# GreenHouse_BOX.net
KiCad netlist of a schematic drawn in EasyEDA
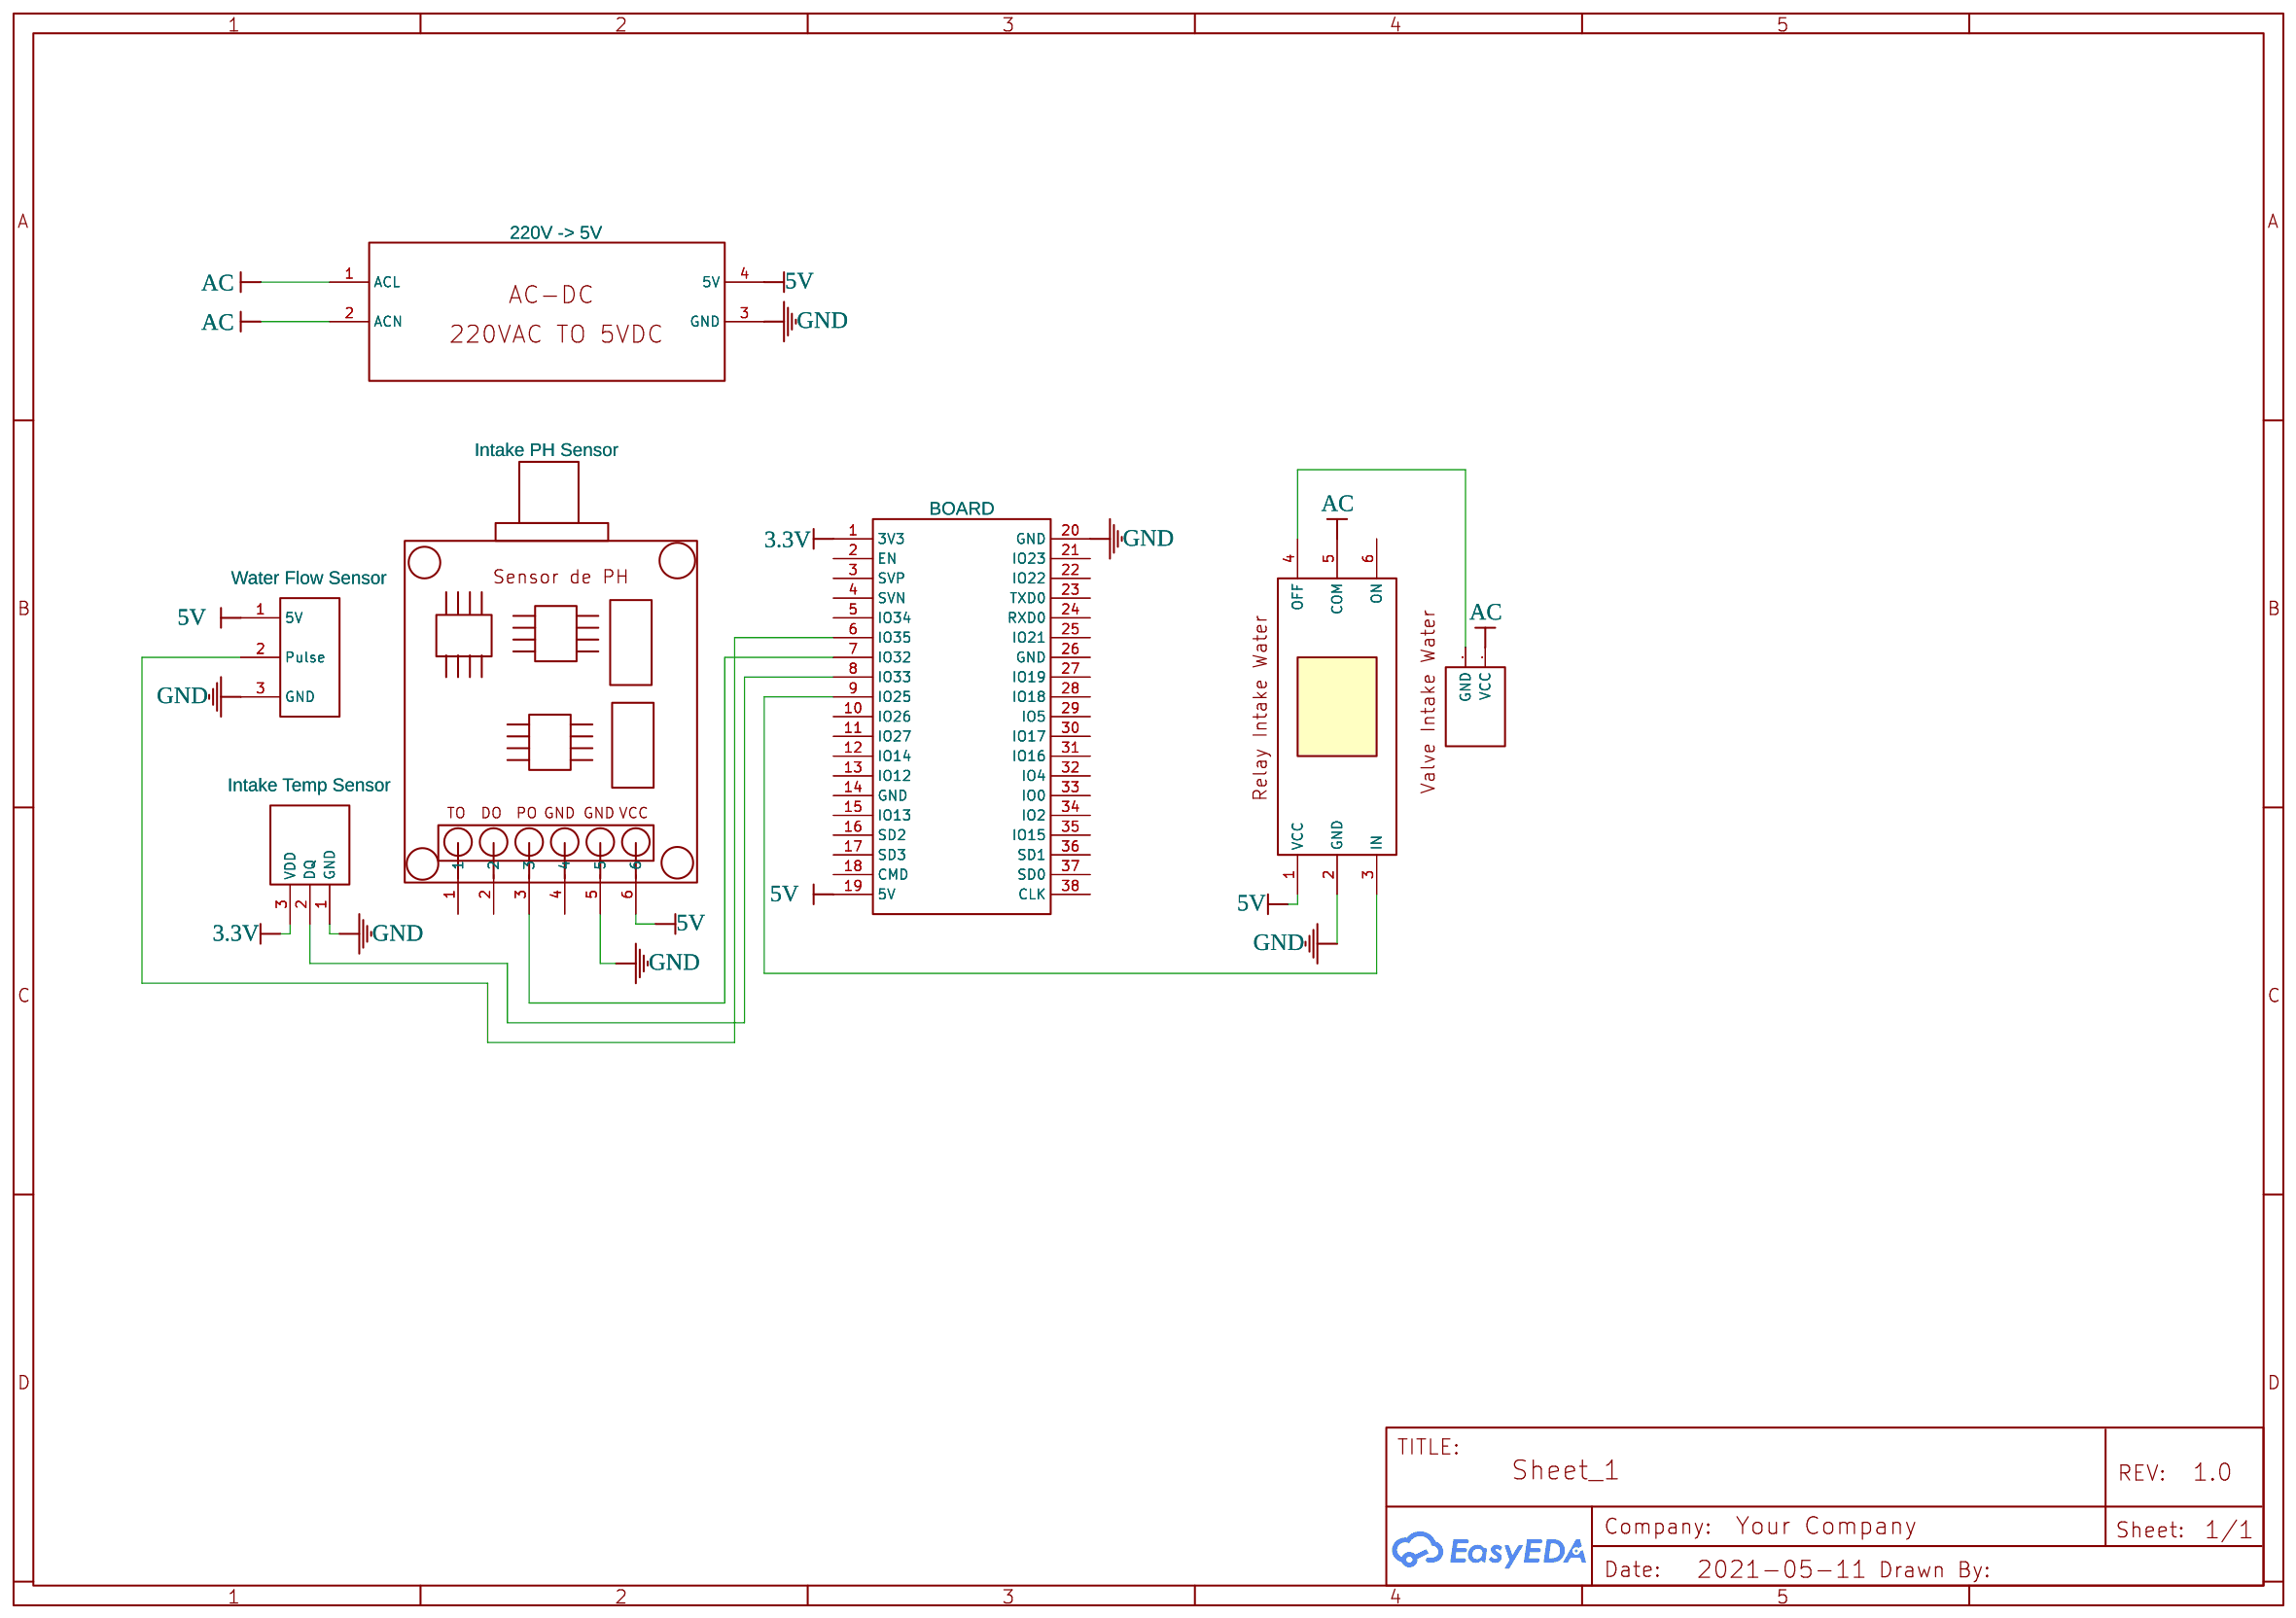
[diagram p0: schematic sheet]

(export (version "E")
  (design (tool "Eeschema 10.0.6"))
  (components
    (comp (ref "BOARD") (value "ESP32") (libsource (lib "") (part "ESP32")))
    (comp (ref "BT1FF")
      (value "Intake Temp Sensor")
      (fields (field (name "BOM_Manufacturer Part") "DS18B20+") (field (name "BOM_Supplier Part") "C9753"))
      (libsource (lib "") (part "DS18B20"))
    )
    (comp (ref "P1")
      (value "Solenoid Valve")
      (fields
        (field (name "BOM_Manufacturer Part") "Header2.54mm 1*3P")
        (field (name "BOM_Supplier Part") "C49257")
      )
      (libsource (lib "") (part "Solenoid Valve"))
    )
    (comp (ref "U1")
      (value "Intake PH Sensor")
      (fields (field (name "BOM_Manufacturer Part") "New SchematicLib"))
      (libsource (lib "") (part "PH Sensor"))
    )
    (comp (ref "U2")
      (value "220V -> 5V")
      (fields (field (name "BOM_Manufacturer Part") "ACDC_220V_5V"))
      (libsource (lib "") (part "ACDC_220V_5V"))
    )
    (comp (ref "U3")
      (value "Arduino Relay 5V 1CH 2LED")
      (fields (field (name "BOM_Manufacturer Part") "Relay module for Arduino"))
      (libsource (lib "") (part "Arduino Relay 5V 1CH 2LED"))
    )
    (comp (ref "U4")
      (value "Water Flow Sensor")
      (fields (field (name "BOM_Manufacturer Part") "Water_flow_sensor"))
      (libsource (lib "") (part "Water_flow_sensor"))
    )
  )
  (nets
    (net (code "1") (name "3.3V") (class "Default")
      (node (ref "BOARD") (pin "1") (pinfunction "3V3_1") (pintype "unspecified"))
      (node (ref "BT1FF") (pin "3") (pinfunction "VDD_3") (pintype "unspecified"))
    )
    (net (code "2") (name "5V") (class "Default")
      (node (ref "BOARD") (pin "19") (pinfunction "5V_19") (pintype "unspecified"))
      (node (ref "U1") (pin "6") (pinfunction "6_6") (pintype "unspecified"))
      (node (ref "U2") (pin "4") (pinfunction "5V_4") (pintype "unspecified"))
      (node (ref "U3") (pin "1") (pinfunction "VCC_1") (pintype "passive"))
      (node (ref "U4") (pin "1") (pinfunction "5V_1") (pintype "unspecified"))
    )
    (net (code "3") (name "AC") (class "Default")
      (node (ref "P1") (pin "1") (pinfunction "VCC_1") (pintype "input"))
      (node (ref "U2") (pin "1") (pinfunction "ACL_1") (pintype "unspecified"))
      (node (ref "U2") (pin "2") (pinfunction "ACN_2") (pintype "unspecified"))
      (node (ref "U3") (pin "5") (pinfunction "COM_5") (pintype "passive"))
    )
    (net (code "4") (name "GND") (class "Default")
      (node (ref "BOARD") (pin "20") (pinfunction "GND_20") (pintype "unspecified"))
      (node (ref "BT1FF") (pin "1") (pinfunction "GND_1") (pintype "unspecified"))
      (node (ref "U1") (pin "5") (pinfunction "5_5") (pintype "unspecified"))
      (node (ref "U2") (pin "3") (pinfunction "GND_3") (pintype "unspecified"))
      (node (ref "U3") (pin "2") (pinfunction "GND_2") (pintype "passive"))
      (node (ref "U4") (pin "3") (pinfunction "GND_3") (pintype "unspecified"))
    )
    (net (code "5") (name "Net-(BOARD-IO25)") (class "Default")
      (node (ref "BOARD") (pin "9") (pinfunction "IO25_9") (pintype "unspecified"))
      (node (ref "U3") (pin "3") (pinfunction "IN_3") (pintype "bidirectional"))
    )
    (net (code "6") (name "Net-(BOARD-IO32)") (class "Default")
      (node (ref "BOARD") (pin "7") (pinfunction "IO32_7") (pintype "unspecified"))
      (node (ref "U1") (pin "3") (pinfunction "3_3") (pintype "unspecified"))
    )
    (net (code "7") (name "Net-(BOARD-IO33)") (class "Default")
      (node (ref "BOARD") (pin "8") (pinfunction "IO33_8") (pintype "unspecified"))
      (node (ref "BT1FF") (pin "2") (pinfunction "DQ_2") (pintype "unspecified"))
    )
    (net (code "8") (name "Net-(BOARD-IO35)") (class "Default")
      (node (ref "BOARD") (pin "6") (pinfunction "IO35_6") (pintype "unspecified"))
      (node (ref "U4") (pin "2") (pinfunction "Pulse_2") (pintype "unspecified"))
    )
    (net (code "9") (name "Net-(P1-GND)") (class "Default")
      (node (ref "P1") (pin "2") (pinfunction "GND_2") (pintype "input"))
      (node (ref "U3") (pin "4") (pinfunction "OFF_4") (pintype "passive"))
    )
    (net (code "10") (name "unconnected-(BOARD-CLK-Pad38)") (class "Default")
      (node (ref "BOARD") (pin "38") (pinfunction "CLK_38") (pintype "unspecified"))
    )
    (net (code "11") (name "unconnected-(BOARD-CMD-Pad18)") (class "Default")
      (node (ref "BOARD") (pin "18") (pinfunction "CMD_18") (pintype "unspecified"))
    )
    (net (code "12") (name "unconnected-(BOARD-EN-Pad2)") (class "Default")
      (node (ref "BOARD") (pin "2") (pinfunction "EN_2") (pintype "unspecified"))
    )
    (net (code "13") (name "unconnected-(BOARD-GND-Pad14)") (class "Default")
      (node (ref "BOARD") (pin "14") (pinfunction "GND_14") (pintype "unspecified"))
    )
    (net (code "14") (name "unconnected-(BOARD-GND-Pad26)") (class "Default")
      (node (ref "BOARD") (pin "26") (pinfunction "GND_26") (pintype "unspecified"))
    )
    (net (code "15") (name "unconnected-(BOARD-IO0-Pad33)") (class "Default")
      (node (ref "BOARD") (pin "33") (pinfunction "IO0_33") (pintype "unspecified"))
    )
    (net (code "16") (name "unconnected-(BOARD-IO2-Pad34)") (class "Default")
      (node (ref "BOARD") (pin "34") (pinfunction "IO2_34") (pintype "unspecified"))
    )
    (net (code "17") (name "unconnected-(BOARD-IO4-Pad32)") (class "Default")
      (node (ref "BOARD") (pin "32") (pinfunction "IO4_32") (pintype "unspecified"))
    )
    (net (code "18") (name "unconnected-(BOARD-IO5-Pad29)") (class "Default")
      (node (ref "BOARD") (pin "29") (pinfunction "IO5_29") (pintype "unspecified"))
    )
    (net (code "19") (name "unconnected-(BOARD-IO12-Pad13)") (class "Default")
      (node (ref "BOARD") (pin "13") (pinfunction "IO12_13") (pintype "unspecified"))
    )
    (net (code "20") (name "unconnected-(BOARD-IO13-Pad15)") (class "Default")
      (node (ref "BOARD") (pin "15") (pinfunction "IO13_15") (pintype "unspecified"))
    )
    (net (code "21") (name "unconnected-(BOARD-IO14-Pad12)") (class "Default")
      (node (ref "BOARD") (pin "12") (pinfunction "IO14_12") (pintype "unspecified"))
    )
    (net (code "22") (name "unconnected-(BOARD-IO15-Pad35)") (class "Default")
      (node (ref "BOARD") (pin "35") (pinfunction "IO15_35") (pintype "unspecified"))
    )
    (net (code "23") (name "unconnected-(BOARD-IO16-Pad31)") (class "Default")
      (node (ref "BOARD") (pin "31") (pinfunction "IO16_31") (pintype "unspecified"))
    )
    (net (code "24") (name "unconnected-(BOARD-IO17-Pad30)") (class "Default")
      (node (ref "BOARD") (pin "30") (pinfunction "IO17_30") (pintype "unspecified"))
    )
    (net (code "25") (name "unconnected-(BOARD-IO18-Pad28)") (class "Default")
      (node (ref "BOARD") (pin "28") (pinfunction "IO18_28") (pintype "unspecified"))
    )
    (net (code "26") (name "unconnected-(BOARD-IO19-Pad27)") (class "Default")
      (node (ref "BOARD") (pin "27") (pinfunction "IO19_27") (pintype "unspecified"))
    )
    (net (code "27") (name "unconnected-(BOARD-IO21-Pad25)") (class "Default")
      (node (ref "BOARD") (pin "25") (pinfunction "IO21_25") (pintype "unspecified"))
    )
    (net (code "28") (name "unconnected-(BOARD-IO22-Pad22)") (class "Default")
      (node (ref "BOARD") (pin "22") (pinfunction "IO22_22") (pintype "unspecified"))
    )
    (net (code "29") (name "unconnected-(BOARD-IO23-Pad21)") (class "Default")
      (node (ref "BOARD") (pin "21") (pinfunction "IO23_21") (pintype "unspecified"))
    )
    (net (code "30") (name "unconnected-(BOARD-IO26-Pad10)") (class "Default")
      (node (ref "BOARD") (pin "10") (pinfunction "IO26_10") (pintype "unspecified"))
    )
    (net (code "31") (name "unconnected-(BOARD-IO27-Pad11)") (class "Default")
      (node (ref "BOARD") (pin "11") (pinfunction "IO27_11") (pintype "unspecified"))
    )
    (net (code "32") (name "unconnected-(BOARD-IO34-Pad5)") (class "Default")
      (node (ref "BOARD") (pin "5") (pinfunction "IO34_5") (pintype "unspecified"))
    )
    (net (code "33") (name "unconnected-(BOARD-RXD0-Pad24)") (class "Default")
      (node (ref "BOARD") (pin "24") (pinfunction "RXD0_24") (pintype "unspecified"))
    )
    (net (code "34") (name "unconnected-(BOARD-SD0-Pad37)") (class "Default")
      (node (ref "BOARD") (pin "37") (pinfunction "SD0_37") (pintype "unspecified"))
    )
    (net (code "35") (name "unconnected-(BOARD-SD1-Pad36)") (class "Default")
      (node (ref "BOARD") (pin "36") (pinfunction "SD1_36") (pintype "unspecified"))
    )
    (net (code "36") (name "unconnected-(BOARD-SD2-Pad16)") (class "Default")
      (node (ref "BOARD") (pin "16") (pinfunction "SD2_16") (pintype "unspecified"))
    )
    (net (code "37") (name "unconnected-(BOARD-SD3-Pad17)") (class "Default")
      (node (ref "BOARD") (pin "17") (pinfunction "SD3_17") (pintype "unspecified"))
    )
    (net (code "38") (name "unconnected-(BOARD-SVN-Pad4)") (class "Default")
      (node (ref "BOARD") (pin "4") (pinfunction "SVN_4") (pintype "unspecified"))
    )
    (net (code "39") (name "unconnected-(BOARD-SVP-Pad3)") (class "Default")
      (node (ref "BOARD") (pin "3") (pinfunction "SVP_3") (pintype "unspecified"))
    )
    (net (code "40") (name "unconnected-(BOARD-TXD0-Pad23)") (class "Default")
      (node (ref "BOARD") (pin "23") (pinfunction "TXD0_23") (pintype "unspecified"))
    )
    (net (code "41") (name "unconnected-(U1-Pad1)") (class "Default")
      (node (ref "U1") (pin "1") (pinfunction "1_1") (pintype "unspecified"))
    )
    (net (code "42") (name "unconnected-(U1-Pad2)") (class "Default")
      (node (ref "U1") (pin "2") (pinfunction "2_2") (pintype "unspecified"))
    )
    (net (code "43") (name "unconnected-(U1-Pad4)") (class "Default")
      (node (ref "U1") (pin "4") (pinfunction "4_4") (pintype "unspecified"))
    )
    (net (code "44") (name "unconnected-(U3-ON-Pad6)") (class "Default")
      (node (ref "U3") (pin "6") (pinfunction "ON_6") (pintype "passive"))
    )
  )
)
